# Door_locking_pcb.net
KiCad netlist of a schematic drawn in EAGLE
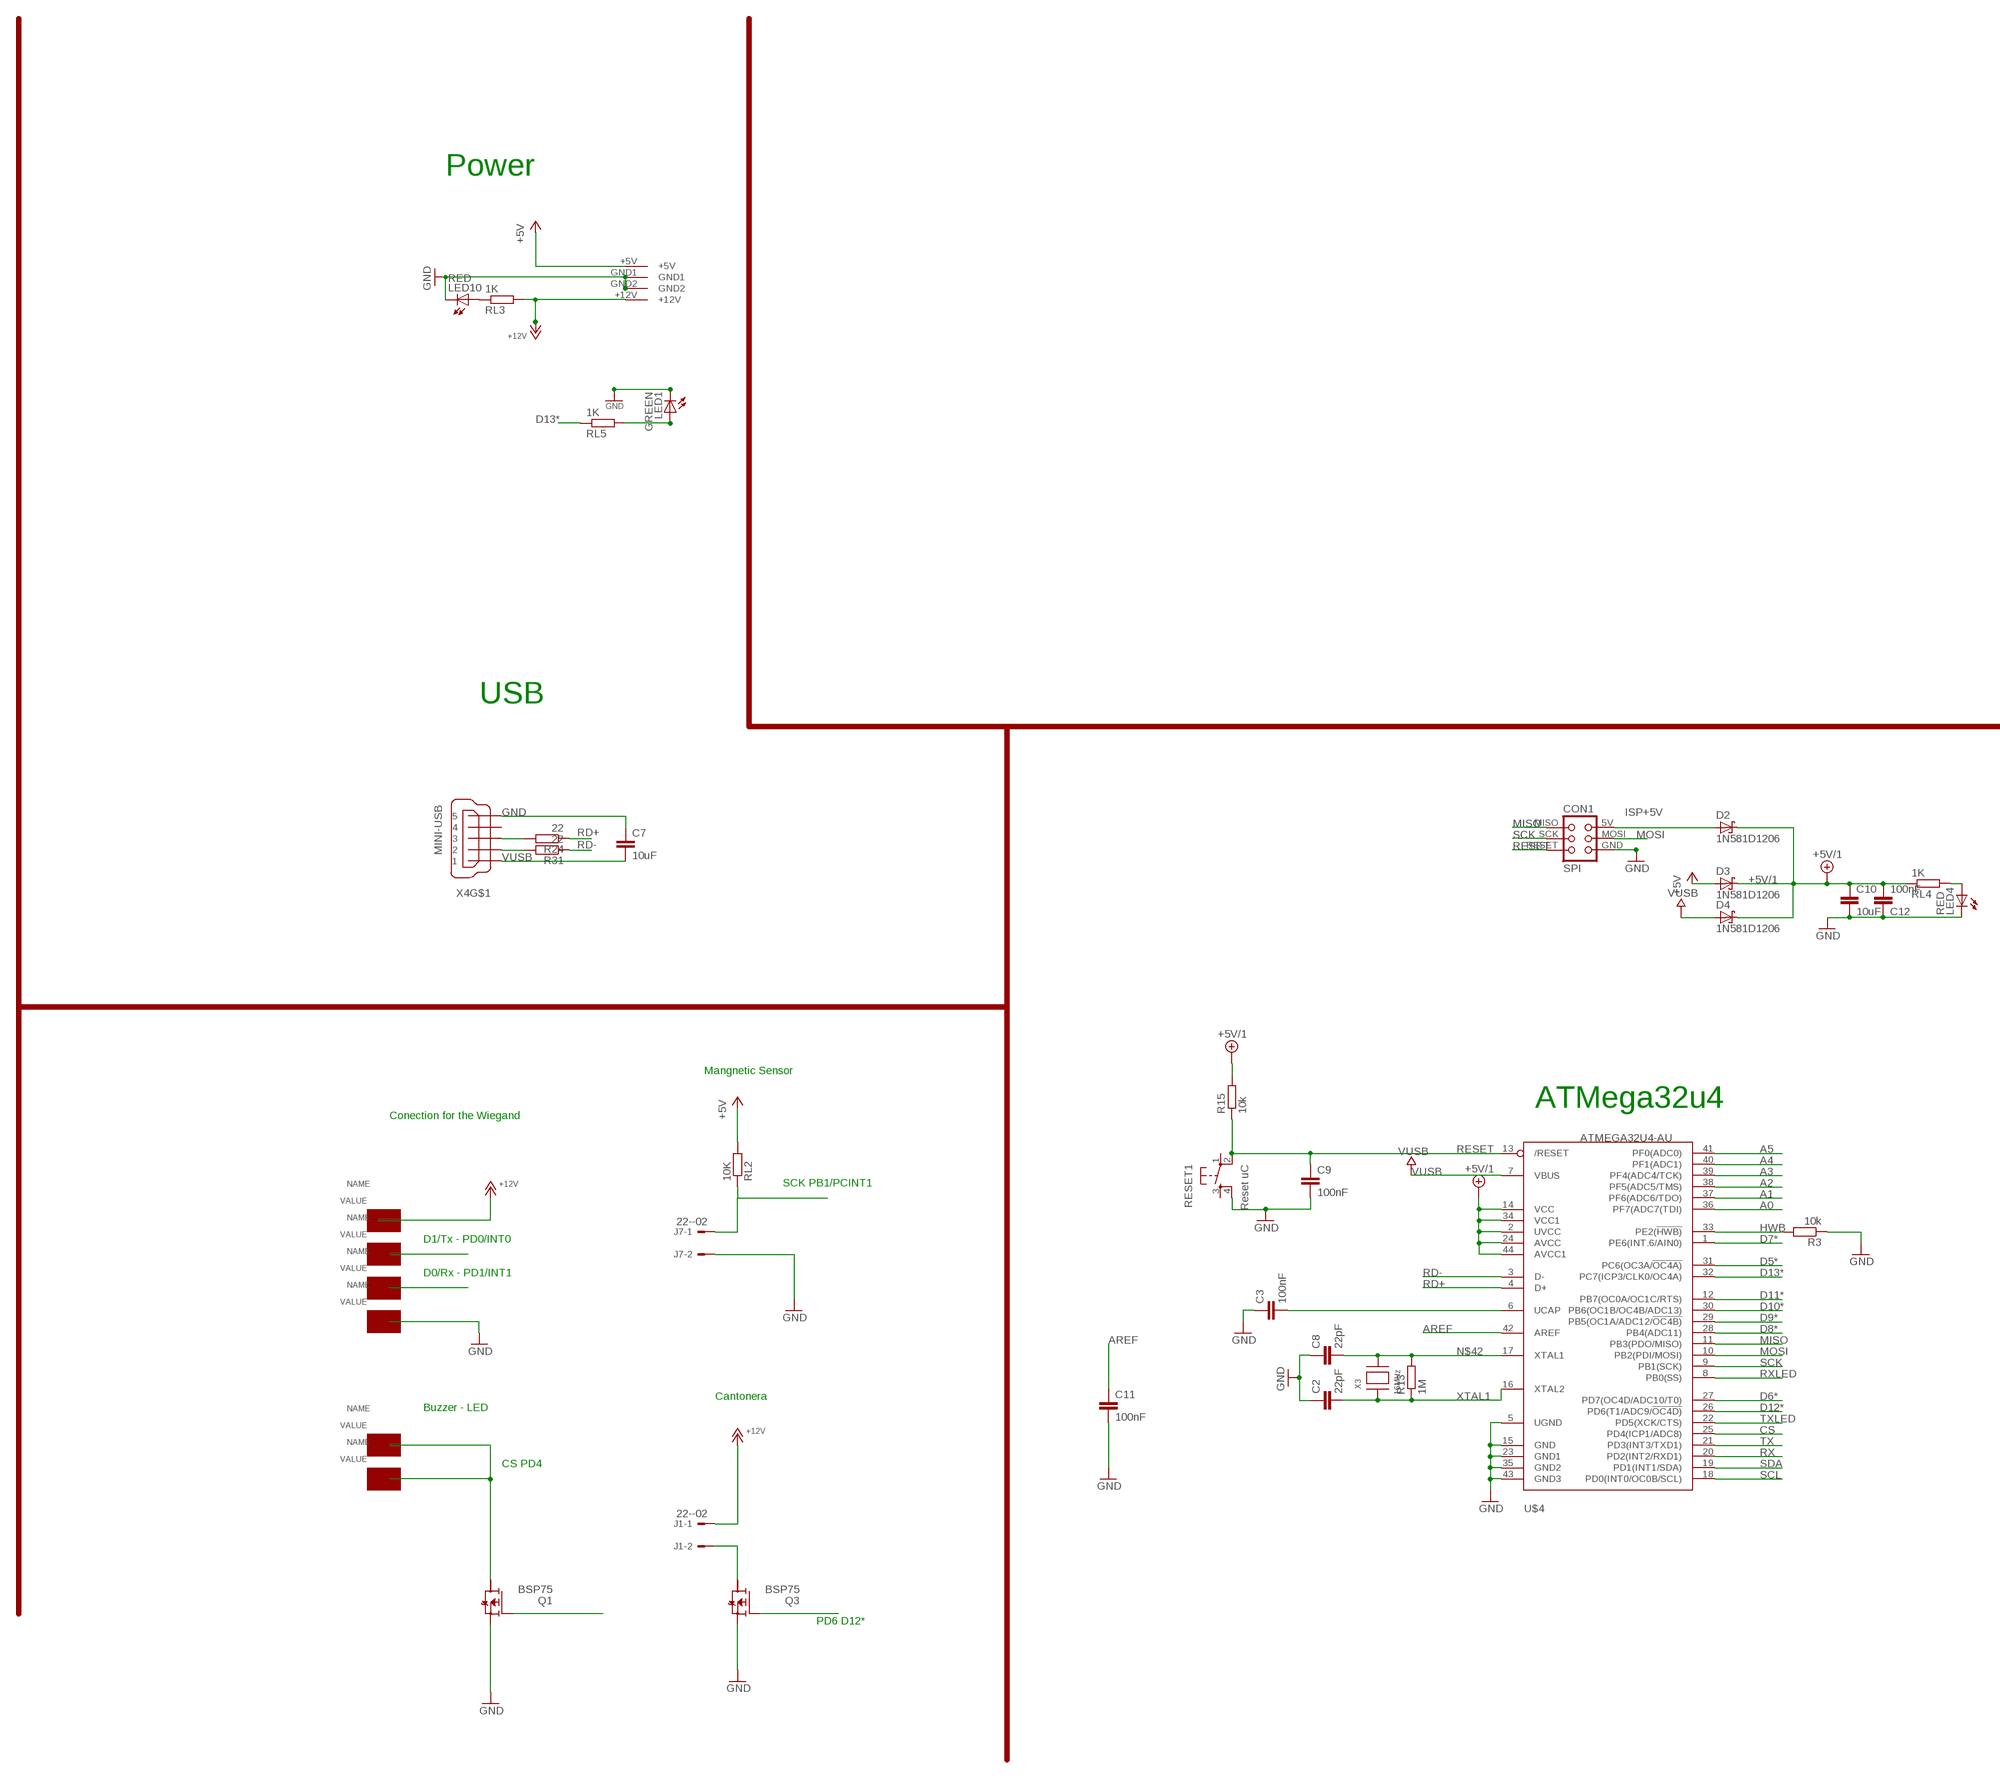
[diagram p0: schematic, sheet 1, part 1 of 2]
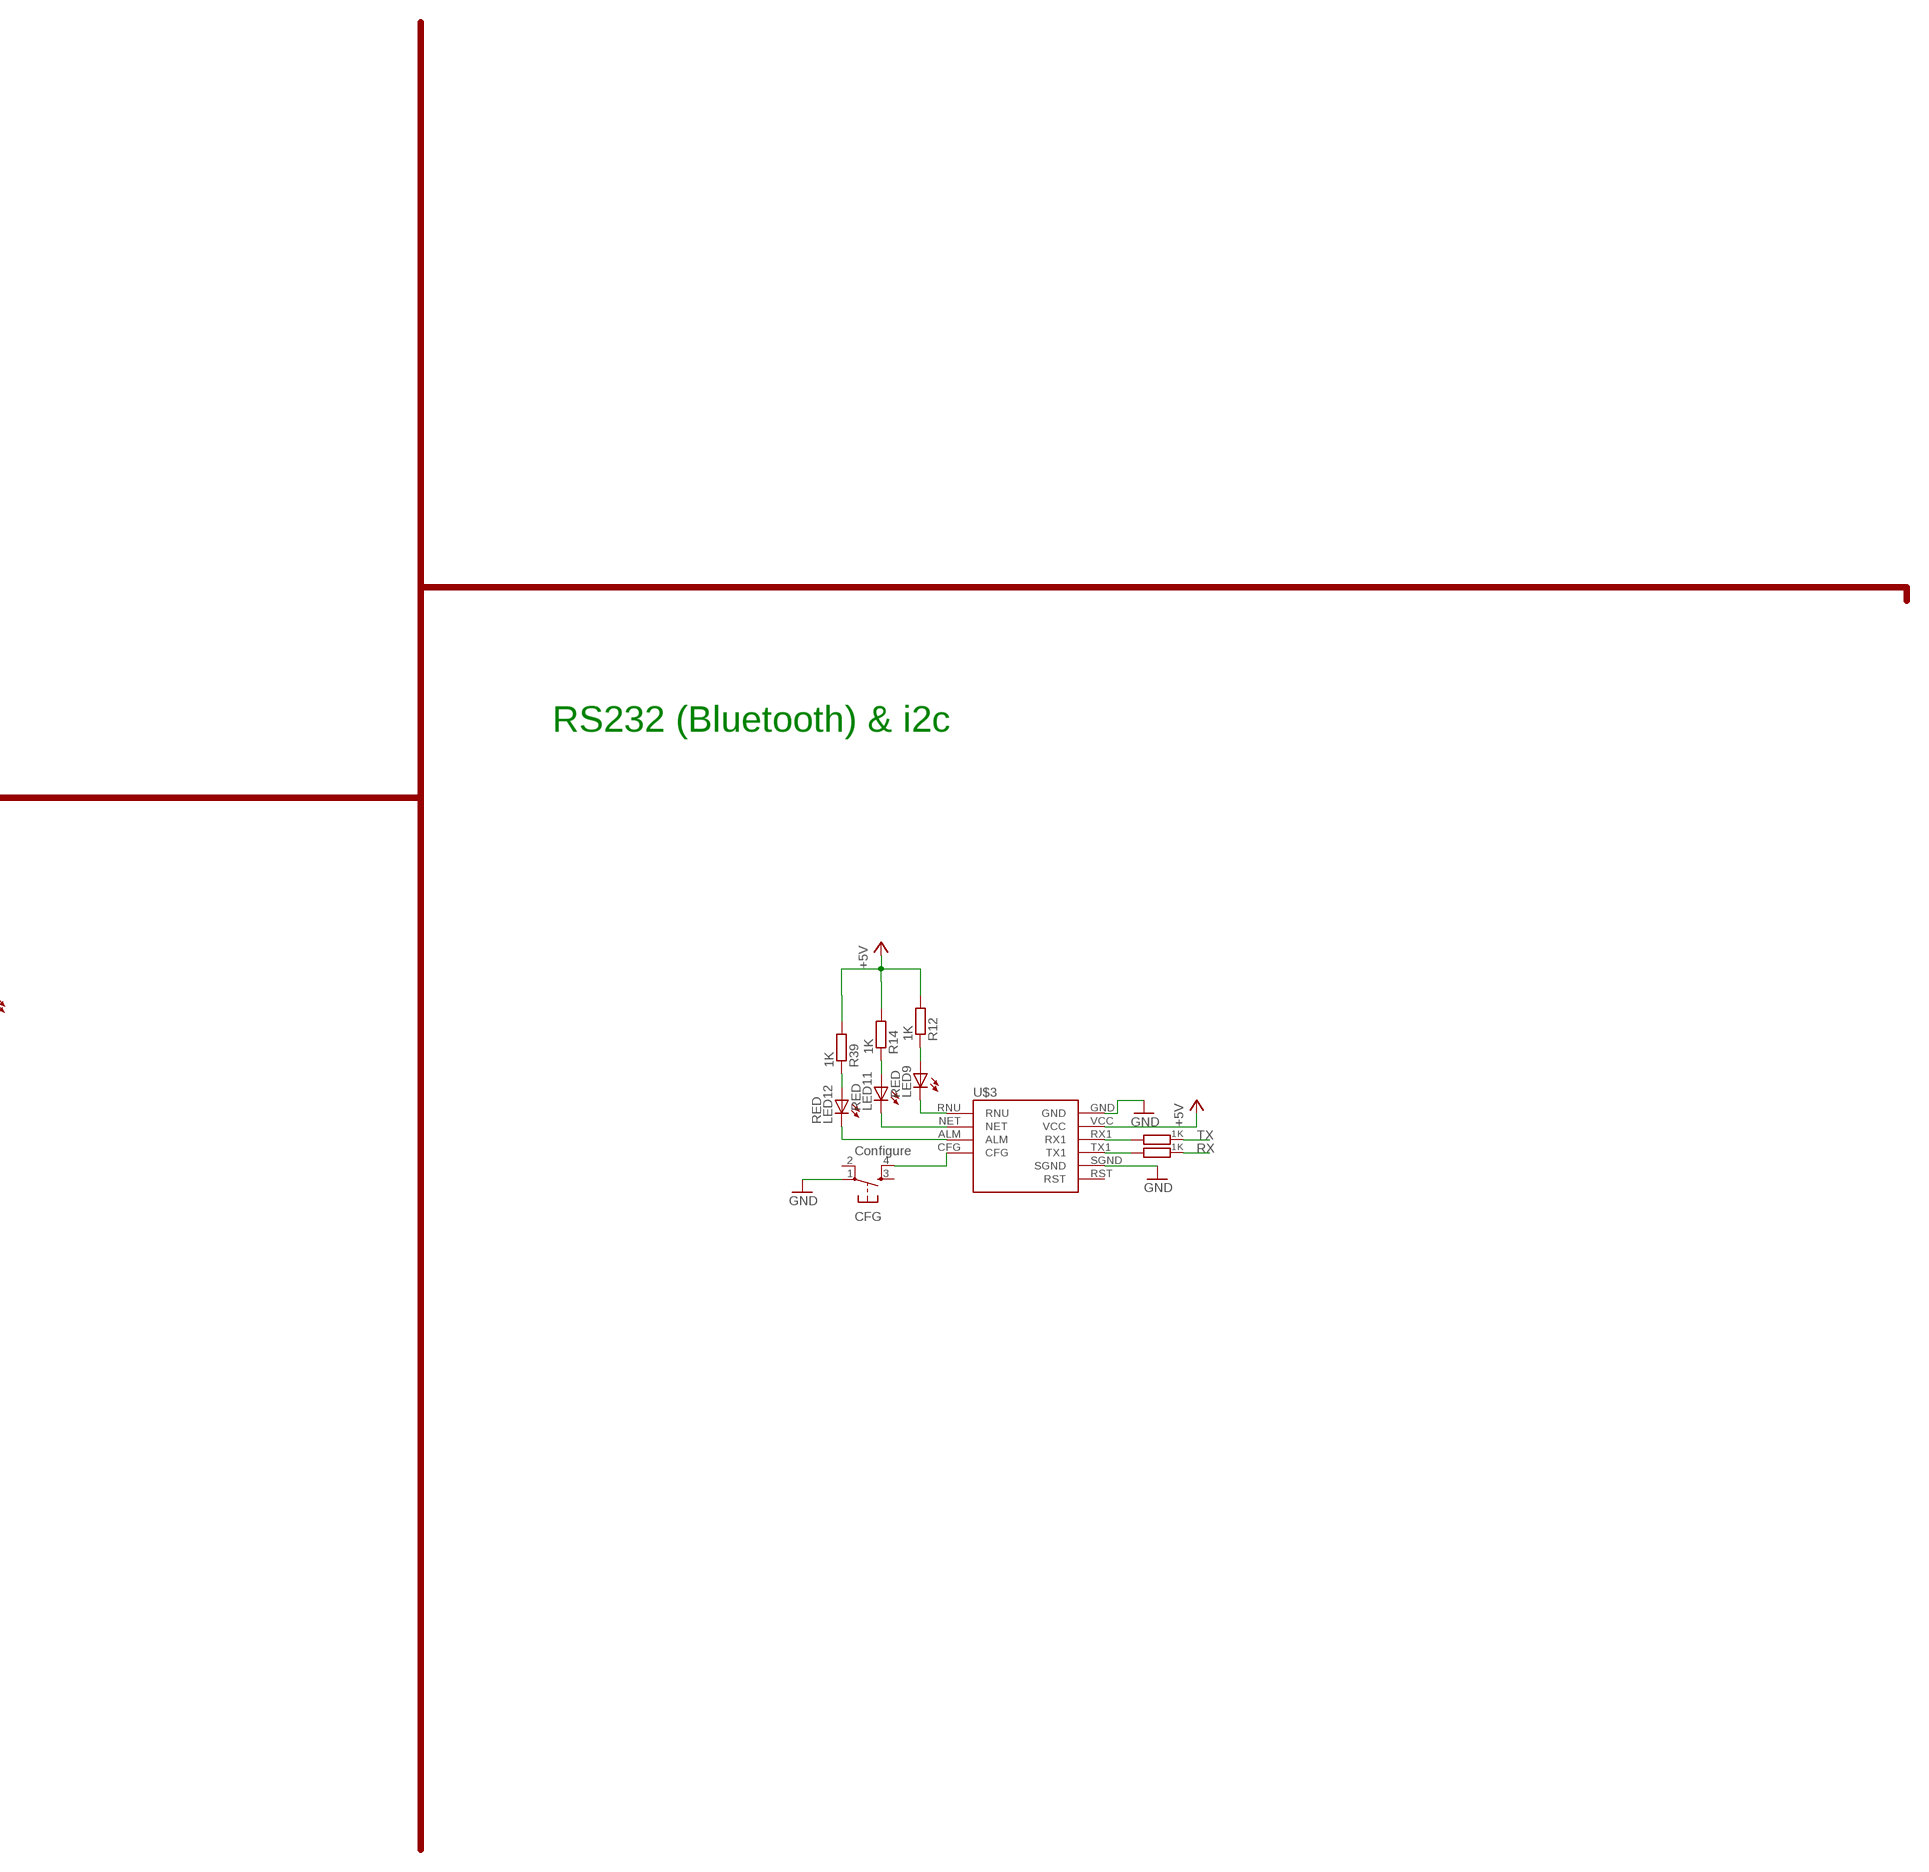
[diagram p1: schematic, sheet 1, part 2 of 2]

(export (version "E")
  (design (tool "Eeschema 10.0.6"))
  (components
    (comp (ref "C2")
      (value "22pF")
      (footprint "eagle-import:C1206")
      (libsource (lib "eagle-import") (part "C-EUC1206"))
    )
    (comp (ref "C3")
      (value "100nF")
      (footprint "eagle-import:C1206")
      (libsource (lib "eagle-import") (part "C-EUC1206"))
    )
    (comp (ref "C7")
      (value "10uF")
      (footprint "eagle-import:C1206")
      (libsource (lib "eagle-import") (part "C-EUC1206"))
    )
    (comp (ref "C8")
      (value "22pF")
      (footprint "eagle-import:C1206")
      (libsource (lib "eagle-import") (part "C-EUC1206"))
    )
    (comp (ref "C9")
      (value "100nF")
      (footprint "eagle-import:C1206")
      (libsource (lib "eagle-import") (part "C-EUC1206"))
    )
    (comp (ref "C10")
      (value "10uF")
      (footprint "eagle-import:C1206")
      (libsource (lib "eagle-import") (part "C-EUC1206"))
    )
    (comp (ref "C11")
      (value "100nF")
      (footprint "eagle-import:C1206")
      (libsource (lib "eagle-import") (part "C-EUC1206"))
    )
    (comp (ref "C12")
      (value "100nF")
      (footprint "eagle-import:C1206")
      (libsource (lib "eagle-import") (part "C-EUC1206"))
    )
    (comp (ref "CFG")
      (value "Configure")
      (footprint "eagle-import:TACTILE_SWITCH_SMD")
      (libsource (lib "eagle-import") (part "TAC_SWITCHSMD"))
    )
    (comp (ref "CON1")
      (value "SPI")
      (footprint "eagle-import:TC2030-MCP-NL")
      (libsource (lib "eagle-import") (part "TINYISPT"))
    )
    (comp (ref "D2")
      (value "1N581D1206")
      (footprint "eagle-import:LED-1206")
      (libsource (lib "eagle-import") (part "1N581D1206"))
    )
    (comp (ref "D3")
      (value "1N581D1206")
      (footprint "eagle-import:LED-1206")
      (libsource (lib "eagle-import") (part "1N581D1206"))
    )
    (comp (ref "D4")
      (value "1N581D1206")
      (footprint "eagle-import:LED-1206")
      (libsource (lib "eagle-import") (part "1N581D1206"))
    )
    (comp (ref "J1")
      (value "22--02")
      (footprint "eagle-import:2-PIN-5.08S")
      (libsource (lib "eagle-import") (part "22-?-02"))
    )
    (comp (ref "J7")
      (value "22--02")
      (footprint "eagle-import:2-PIN-5.08S")
      (libsource (lib "eagle-import") (part "22-?-02"))
    )
    (comp (ref "LED1")
      (value "GREEN")
      (footprint "eagle-import:CHIPLED_1206")
      (libsource (lib "eagle-import") (part "LEDCHIPLED_1206"))
    )
    (comp (ref "LED4")
      (value "RED")
      (footprint "eagle-import:CHIPLED_1206")
      (libsource (lib "eagle-import") (part "LEDCHIPLED_1206"))
    )
    (comp (ref "LED9")
      (value "RED")
      (footprint "eagle-import:CHIPLED_1206")
      (libsource (lib "eagle-import") (part "LEDCHIPLED_1206"))
    )
    (comp (ref "LED10")
      (value "RED")
      (footprint "eagle-import:CHIPLED_1206")
      (libsource (lib "eagle-import") (part "LEDCHIPLED_1206"))
    )
    (comp (ref "LED11")
      (value "RED")
      (footprint "eagle-import:CHIPLED_1206")
      (libsource (lib "eagle-import") (part "LEDCHIPLED_1206"))
    )
    (comp (ref "LED12")
      (value "RED")
      (footprint "eagle-import:CHIPLED_1206")
      (libsource (lib "eagle-import") (part "LEDCHIPLED_1206"))
    )
    (comp (ref "PIN1")
      (value "TERMINALSUPERFICIAL")
      (footprint "eagle-import:ELPUTAS")
      (libsource (lib "eagle-import") (part "TERMINALSUPERFICIAL"))
    )
    (comp (ref "PIN2")
      (value "TERMINALSUPERFICIAL")
      (footprint "eagle-import:ELPUTAS")
      (libsource (lib "eagle-import") (part "TERMINALSUPERFICIAL"))
    )
    (comp (ref "PIN3")
      (value "TERMINALSUPERFICIAL")
      (footprint "eagle-import:ELPUTAS")
      (libsource (lib "eagle-import") (part "TERMINALSUPERFICIAL"))
    )
    (comp (ref "PIN4")
      (value "TERMINALSUPERFICIAL")
      (footprint "eagle-import:ELPUTAS")
      (libsource (lib "eagle-import") (part "TERMINALSUPERFICIAL"))
    )
    (comp (ref "PIN5")
      (value "TERMINALSUPERFICIAL")
      (footprint "eagle-import:ELPUTAS")
      (libsource (lib "eagle-import") (part "TERMINALSUPERFICIAL"))
    )
    (comp (ref "PIN6")
      (value "TERMINALSUPERFICIAL")
      (footprint "eagle-import:ELPUTAS")
      (libsource (lib "eagle-import") (part "TERMINALSUPERFICIAL"))
    )
    (comp (ref "Q1")
      (value "BSP75")
      (footprint "eagle-import:PG-SOT-223")
      (libsource (lib "eagle-import") (part "BSP613P"))
    )
    (comp (ref "Q3")
      (value "BSP75")
      (footprint "eagle-import:PG-SOT-223")
      (libsource (lib "eagle-import") (part "BSP613P"))
    )
    (comp (ref "R3")
      (value "10k")
      (footprint "eagle-import:M0805")
      (libsource (lib "eagle-import") (part "resistor_R-EU_M0805"))
    )
    (comp (ref "R8")
      (value "1K")
      (footprint "eagle-import:R0805")
      (libsource (lib "eagle-import") (part "R-EU_R0805"))
    )
    (comp (ref "R11")
      (value "1K")
      (footprint "eagle-import:R0805")
      (libsource (lib "eagle-import") (part "R-EU_R0805"))
    )
    (comp (ref "R12")
      (value "1K")
      (footprint "eagle-import:R0805")
      (libsource (lib "eagle-import") (part "R-EU_R0805"))
    )
    (comp (ref "R13")
      (value "1M")
      (footprint "eagle-import:R1206")
      (libsource (lib "eagle-import") (part "R-EU_R1206"))
    )
    (comp (ref "R14")
      (value "1K")
      (footprint "eagle-import:R0805")
      (libsource (lib "eagle-import") (part "R-EU_R0805"))
    )
    (comp (ref "R15")
      (value "10k")
      (footprint "eagle-import:M0805")
      (libsource (lib "eagle-import") (part "resistor_R-EU_M0805"))
    )
    (comp (ref "R24")
      (value "22")
      (footprint "eagle-import:M1206")
      (libsource (lib "eagle-import") (part "resistor_R-EU_M1206"))
    )
    (comp (ref "R31")
      (value "22")
      (footprint "eagle-import:M1206")
      (libsource (lib "eagle-import") (part "resistor_R-EU_M1206"))
    )
    (comp (ref "R39")
      (value "1K")
      (footprint "eagle-import:R0805")
      (libsource (lib "eagle-import") (part "R-EU_R0805"))
    )
    (comp (ref "RESET1")
      (value "Reset uC")
      (footprint "eagle-import:TACTILE_SWITCH_SMD")
      (libsource (lib "eagle-import") (part "TAC_SWITCHSMD"))
    )
    (comp (ref "RL2")
      (value "10K")
      (footprint "eagle-import:R0805")
      (libsource (lib "eagle-import") (part "R-EU_R0805"))
    )
    (comp (ref "RL3")
      (value "1K")
      (footprint "eagle-import:R0805")
      (libsource (lib "eagle-import") (part "R-EU_R0805"))
    )
    (comp (ref "RL4")
      (value "1K")
      (footprint "eagle-import:R0805")
      (libsource (lib "eagle-import") (part "resistor_R-EU_R0805"))
    )
    (comp (ref "RL5")
      (value "1K")
      (footprint "eagle-import:R0805")
      (libsource (lib "eagle-import") (part "R-EU_R0805"))
    )
    (comp (ref "U$3")
      (value "SZ05-ZIGBEE")
      (footprint "eagle-import:SZ05-ZIGBEE")
      (libsource (lib "eagle-import") (part "SZ05-ZIGBEE"))
    )
    (comp (ref "U$4")
      (value "ATMEGA32U4-AU")
      (footprint "eagle-import:TQFP44")
      (libsource (lib "eagle-import") (part "ATMEGA32U4-AU"))
    )
    (comp (ref "U$6")
      (value "KPJX-4S-S")
      (footprint "eagle-import:KPJX-4S-S")
      (libsource (lib "eagle-import") (part "KPJX-4S-S"))
    )
    (comp (ref "X3")
      (value "16MHz")
      (footprint "eagle-import:NX6035")
      (libsource (lib "eagle-import") (part "XTALNX6035"))
    )
    (comp (ref "X4")
      (value "MINI-USB")
      (footprint "eagle-import:32005-201")
      (libsource (lib "eagle-import") (part "MINI-USB-SCHIELD-32005-201"))
    )
  )
  (nets
    (net (code "1") (name "+5V") (class "Default")
      (node (ref "D3") (pin "A") (pinfunction "A_A") (pintype "passive"))
      (node (ref "R12") (pin "2") (pinfunction "2_2") (pintype "passive"))
      (node (ref "R14") (pin "2") (pinfunction "2_2") (pintype "passive"))
      (node (ref "R39") (pin "2") (pinfunction "2_2") (pintype "passive"))
      (node (ref "RL2") (pin "2") (pinfunction "2_2") (pintype "passive"))
      (node (ref "U$3") (pin "VCC") (pinfunction "VCC_VCC") (pintype "bidirectional"))
      (node (ref "U$6") (pin "+5V") (pinfunction "+5V_+5V") (pintype "power_in"))
    )
    (net (code "2") (name "+5V{slash}1") (class "Default")
      (node (ref "C10") (pin "1") (pinfunction "1_1") (pintype "passive"))
      (node (ref "C12") (pin "2") (pinfunction "2_2") (pintype "passive"))
      (node (ref "D2") (pin "C") (pinfunction "C_C") (pintype "passive"))
      (node (ref "D3") (pin "C") (pinfunction "C_C") (pintype "passive"))
      (node (ref "D4") (pin "C") (pinfunction "C_C") (pintype "passive"))
      (node (ref "R15") (pin "2") (pinfunction "2_2") (pintype "passive"))
      (node (ref "RL4") (pin "1") (pinfunction "1_1") (pintype "passive"))
      (node (ref "U$4") (pin "14") (pinfunction "VCC_14") (pintype "bidirectional"))
      (node (ref "U$4") (pin "2") (pinfunction "UVCC_2") (pintype "bidirectional"))
      (node (ref "U$4") (pin "24") (pinfunction "AVCC_24") (pintype "bidirectional"))
      (node (ref "U$4") (pin "34") (pinfunction "VCC1_34") (pintype "bidirectional"))
      (node (ref "U$4") (pin "44") (pinfunction "AVCC1_44") (pintype "bidirectional"))
    )
    (net (code "3") (name "+12V") (class "Default")
      (node (ref "J1") (pin "1") (pinfunction "S_1") (pintype "passive"))
      (node (ref "PIN6") (pin "P$4") (pinfunction "2_P$4") (pintype "bidirectional"))
      (node (ref "RL3") (pin "2") (pinfunction "2_2") (pintype "passive"))
      (node (ref "U$6") (pin "+12V") (pinfunction "+12V_+12V") (pintype "power_in"))
    )
    (net (code "4") (name "/A0") (class "Default")
      (node (ref "U$4") (pin "36") (pinfunction "PF7(ADC7(TDI)_36") (pintype "bidirectional"))
    )
    (net (code "5") (name "/A1") (class "Default")
      (node (ref "U$4") (pin "37") (pinfunction "PF6(ADC6/TDO)_37") (pintype "bidirectional"))
    )
    (net (code "6") (name "/A2") (class "Default")
      (node (ref "U$4") (pin "38") (pinfunction "PF5(ADC5/TMS)_38") (pintype "bidirectional"))
    )
    (net (code "7") (name "/A3") (class "Default")
      (node (ref "U$4") (pin "39") (pinfunction "PF4(ADC4/TCK)_39") (pintype "bidirectional"))
    )
    (net (code "8") (name "/A4") (class "Default")
      (node (ref "U$4") (pin "40") (pinfunction "PF1(ADC1)_40") (pintype "bidirectional"))
    )
    (net (code "9") (name "/A5") (class "Default")
      (node (ref "U$4") (pin "41") (pinfunction "PF0(ADC0)_41") (pintype "bidirectional"))
    )
    (net (code "10") (name "/AREF") (class "Default")
      (node (ref "C11") (pin "1") (pinfunction "1_1") (pintype "passive"))
      (node (ref "U$4") (pin "42") (pinfunction "AREF_42") (pintype "bidirectional"))
    )
    (net (code "11") (name "/CS") (class "Default")
      (node (ref "Q1") (pin "1") (pinfunction "G_1") (pintype "passive"))
      (node (ref "U$4") (pin "25") (pinfunction "PD4(ICP1/ADC8)_25") (pintype "bidirectional"))
    )
    (net (code "12") (name "/D5*") (class "Default")
      (node (ref "U$4") (pin "31") (pinfunction "PC6(OC3A/~{OC4A})_31") (pintype "bidirectional"))
    )
    (net (code "13") (name "/D6*") (class "Default")
      (node (ref "U$4") (pin "27") (pinfunction "PD7(OC4D/ADC10/T0)_27") (pintype "bidirectional"))
    )
    (net (code "14") (name "/D7*") (class "Default")
      (node (ref "U$4") (pin "1") (pinfunction "PE6(INT.6/AIN0)_1") (pintype "bidirectional"))
    )
    (net (code "15") (name "/D8*") (class "Default")
      (node (ref "U$4") (pin "28") (pinfunction "PB4(ADC11)_28") (pintype "bidirectional"))
    )
    (net (code "16") (name "/D9*") (class "Default")
      (node (ref "U$4") (pin "29") (pinfunction "PB5(OC1A/ADC12/~{OC4B})_29") (pintype "bidirectional"))
    )
    (net (code "17") (name "/D10*") (class "Default")
      (node (ref "U$4") (pin "30") (pinfunction "PB6(OC1B/OC4B/ADC13)_30") (pintype "bidirectional"))
    )
    (net (code "18") (name "/D11*") (class "Default")
      (node (ref "U$4") (pin "12") (pinfunction "PB7(OC0A/OC1C/RTS)_12") (pintype "bidirectional"))
    )
    (net (code "19") (name "/D12*") (class "Default")
      (node (ref "Q3") (pin "1") (pinfunction "G_1") (pintype "passive"))
      (node (ref "U$4") (pin "26") (pinfunction "PD6(T1/ADC9/~{OC4D})_26") (pintype "bidirectional"))
    )
    (net (code "20") (name "/D13*") (class "Default")
      (node (ref "RL5") (pin "1") (pinfunction "1_1") (pintype "passive"))
      (node (ref "U$4") (pin "32") (pinfunction "PC7(ICP3/CLK0/OC4A)_32") (pintype "bidirectional"))
    )
    (net (code "21") (name "/HWB") (class "Default")
      (node (ref "R3") (pin "2") (pinfunction "2_2") (pintype "passive"))
      (node (ref "U$4") (pin "33") (pinfunction "PE2(~{HWB})_33") (pintype "bidirectional"))
    )
    (net (code "22") (name "/ISP+5V") (class "Default")
      (node (ref "CON1") (pin "5V") (pinfunction "VCC_5V") (pintype "passive"))
      (node (ref "D2") (pin "A") (pinfunction "A_A") (pintype "passive"))
    )
    (net (code "23") (name "/MISO") (class "Default")
      (node (ref "CON1") (pin "MISO") (pinfunction "MISO_MISO") (pintype "passive"))
      (node (ref "U$4") (pin "11") (pinfunction "PB3(PDO/MISO)_11") (pintype "bidirectional"))
    )
    (net (code "24") (name "/MOSI") (class "Default")
      (node (ref "CON1") (pin "MOSI") (pinfunction "MOSI_MOSI") (pintype "passive"))
      (node (ref "U$4") (pin "10") (pinfunction "PB2(PDI/MOSI)_10") (pintype "bidirectional"))
    )
    (net (code "25") (name "/N$42") (class "Default")
      (node (ref "C8") (pin "2") (pinfunction "2_2") (pintype "passive"))
      (node (ref "R13") (pin "2") (pinfunction "2_2") (pintype "passive"))
      (node (ref "U$4") (pin "17") (pinfunction "XTAL1_17") (pintype "bidirectional"))
      (node (ref "X3") (pin "P$2") (pinfunction "P$2_P$2") (pintype "bidirectional"))
    )
    (net (code "26") (name "/RD+") (class "Default")
      (node (ref "R24") (pin "1") (pinfunction "1_1") (pintype "passive"))
      (node (ref "U$4") (pin "4") (pinfunction "D+_4") (pintype "bidirectional"))
    )
    (net (code "27") (name "/RD-") (class "Default")
      (node (ref "R31") (pin "1") (pinfunction "1_1") (pintype "passive"))
      (node (ref "U$4") (pin "3") (pinfunction "D-_3") (pintype "bidirectional"))
    )
    (net (code "28") (name "/RESET") (class "Default")
      (node (ref "C9") (pin "1") (pinfunction "1_1") (pintype "passive"))
      (node (ref "CON1") (pin "RESET") (pinfunction "RESET_RESET") (pintype "passive"))
      (node (ref "R15") (pin "1") (pinfunction "1_1") (pintype "passive"))
      (node (ref "RESET1") (pin "2") (pinfunction "2_2") (pintype "passive"))
      (node (ref "U$4") (pin "13") (pinfunction "/RESET_13") (pintype "bidirectional"))
    )
    (net (code "29") (name "/RX") (class "Default")
      (node (ref "R8") (pin "1") (pinfunction "1_1") (pintype "passive"))
      (node (ref "U$4") (pin "20") (pinfunction "PD2(INT2/RXD1)_20") (pintype "bidirectional"))
    )
    (net (code "30") (name "/RXLED") (class "Default")
      (node (ref "U$4") (pin "8") (pinfunction "PB0(SS)_8") (pintype "bidirectional"))
    )
    (net (code "31") (name "/SCK") (class "Default")
      (node (ref "CON1") (pin "SCK") (pinfunction "SCK_SCK") (pintype "passive"))
      (node (ref "J7") (pin "1") (pinfunction "S_1") (pintype "passive"))
      (node (ref "RL2") (pin "1") (pinfunction "1_1") (pintype "passive"))
      (node (ref "U$4") (pin "9") (pinfunction "PB1(SCK)_9") (pintype "bidirectional"))
    )
    (net (code "32") (name "/SCL") (class "Default")
      (node (ref "PIN1") (pin "P$3") (pinfunction "1_P$3") (pintype "bidirectional"))
      (node (ref "U$4") (pin "18") (pinfunction "PD0(INT0/OC0B/SCL)_18") (pintype "bidirectional"))
    )
    (net (code "33") (name "/SDA") (class "Default")
      (node (ref "PIN2") (pin "P$3") (pinfunction "1_P$3") (pintype "bidirectional"))
      (node (ref "U$4") (pin "19") (pinfunction "PD1(INT1/SDA)_19") (pintype "bidirectional"))
    )
    (net (code "34") (name "/TX") (class "Default")
      (node (ref "R11") (pin "1") (pinfunction "1_1") (pintype "passive"))
      (node (ref "U$4") (pin "21") (pinfunction "PD3(INT3/TXD1)_21") (pintype "bidirectional"))
    )
    (net (code "35") (name "/TXLED") (class "Default")
      (node (ref "U$4") (pin "22") (pinfunction "PD5(XCK/CTS)_22") (pintype "bidirectional"))
    )
    (net (code "36") (name "/XTAL1") (class "Default")
      (node (ref "C2") (pin "2") (pinfunction "2_2") (pintype "passive"))
      (node (ref "R13") (pin "1") (pinfunction "1_1") (pintype "passive"))
      (node (ref "U$4") (pin "16") (pinfunction "XTAL2_16") (pintype "bidirectional"))
      (node (ref "X3") (pin "P$1") (pinfunction "P$1_P$1") (pintype "bidirectional"))
    )
    (net (code "37") (name "GND") (class "Default")
      (node (ref "C10") (pin "2") (pinfunction "2_2") (pintype "passive"))
      (node (ref "C11") (pin "2") (pinfunction "2_2") (pintype "passive"))
      (node (ref "C12") (pin "1") (pinfunction "1_1") (pintype "passive"))
      (node (ref "C2") (pin "1") (pinfunction "1_1") (pintype "passive"))
      (node (ref "C3") (pin "1") (pinfunction "1_1") (pintype "passive"))
      (node (ref "C7") (pin "1") (pinfunction "1_1") (pintype "passive"))
      (node (ref "C8") (pin "1") (pinfunction "1_1") (pintype "passive"))
      (node (ref "C9") (pin "2") (pinfunction "2_2") (pintype "passive"))
      (node (ref "CFG") (pin "1") (pinfunction "1_1") (pintype "passive"))
      (node (ref "CON1") (pin "GND") (pinfunction "GND_GND") (pintype "passive"))
      (node (ref "J7") (pin "2") (pinfunction "S_2") (pintype "passive"))
      (node (ref "LED1") (pin "C") (pinfunction "C_C") (pintype "passive"))
      (node (ref "LED10") (pin "C") (pinfunction "C_C") (pintype "passive"))
      (node (ref "LED4") (pin "C") (pinfunction "C_C") (pintype "passive"))
      (node (ref "PIN5") (pin "P$3") (pinfunction "1_P$3") (pintype "bidirectional"))
      (node (ref "Q1") (pin "3") (pinfunction "S_3") (pintype "passive"))
      (node (ref "Q3") (pin "3") (pinfunction "S_3") (pintype "passive"))
      (node (ref "R3") (pin "1") (pinfunction "1_1") (pintype "passive"))
      (node (ref "RESET1") (pin "4") (pinfunction "4_4") (pintype "passive"))
      (node (ref "U$3") (pin "GND") (pinfunction "GND_GND") (pintype "bidirectional"))
      (node (ref "U$3") (pin "SGND") (pinfunction "SGND_SGND") (pintype "bidirectional"))
      (node (ref "U$4") (pin "15") (pinfunction "GND_15") (pintype "bidirectional"))
      (node (ref "U$4") (pin "23") (pinfunction "GND1_23") (pintype "bidirectional"))
      (node (ref "U$4") (pin "35") (pinfunction "GND2_35") (pintype "bidirectional"))
      (node (ref "U$4") (pin "43") (pinfunction "GND3_43") (pintype "bidirectional"))
      (node (ref "U$4") (pin "5") (pinfunction "UGND_5") (pintype "bidirectional"))
      (node (ref "U$6") (pin "GND1") (pinfunction "GND1_GND1") (pintype "input"))
      (node (ref "U$6") (pin "GND2") (pinfunction "GND2_GND2") (pintype "input"))
      (node (ref "X4") (pin "5") (pinfunction "5_5") (pintype "passive"))
    )
    (net (code "38") (name "Net-(CFG-Pad4)") (class "Default")
      (node (ref "CFG") (pin "4") (pinfunction "4_4") (pintype "passive"))
      (node (ref "U$3") (pin "CFG") (pinfunction "CFG_CFG") (pintype "bidirectional"))
    )
    (net (code "39") (name "Net-(J1B-S)") (class "Default")
      (node (ref "J1") (pin "2") (pinfunction "S_2") (pintype "passive"))
      (node (ref "Q3") (pin "2") (pinfunction "D_2") (pintype "passive"))
    )
    (net (code "40") (name "Net-(LED1-PadA)") (class "Default")
      (node (ref "LED1") (pin "A") (pinfunction "A_A") (pintype "passive"))
      (node (ref "RL5") (pin "2") (pinfunction "2_2") (pintype "passive"))
    )
    (net (code "41") (name "Net-(LED4-PadA)") (class "Default")
      (node (ref "LED4") (pin "A") (pinfunction "A_A") (pintype "passive"))
      (node (ref "RL4") (pin "2") (pinfunction "2_2") (pintype "passive"))
    )
    (net (code "42") (name "Net-(LED9-PadA)") (class "Default")
      (node (ref "LED9") (pin "A") (pinfunction "A_A") (pintype "passive"))
      (node (ref "R12") (pin "1") (pinfunction "1_1") (pintype "passive"))
    )
    (net (code "43") (name "Net-(LED9-PadC)") (class "Default")
      (node (ref "LED9") (pin "C") (pinfunction "C_C") (pintype "passive"))
      (node (ref "U$3") (pin "RNU") (pinfunction "RNU_RNU") (pintype "bidirectional"))
    )
    (net (code "44") (name "Net-(LED10-PadA)") (class "Default")
      (node (ref "LED10") (pin "A") (pinfunction "A_A") (pintype "passive"))
      (node (ref "RL3") (pin "1") (pinfunction "1_1") (pintype "passive"))
    )
    (net (code "45") (name "Net-(LED11-PadA)") (class "Default")
      (node (ref "LED11") (pin "A") (pinfunction "A_A") (pintype "passive"))
      (node (ref "R14") (pin "1") (pinfunction "1_1") (pintype "passive"))
    )
    (net (code "46") (name "Net-(LED11-PadC)") (class "Default")
      (node (ref "LED11") (pin "C") (pinfunction "C_C") (pintype "passive"))
      (node (ref "U$3") (pin "NET") (pinfunction "NET_NET") (pintype "bidirectional"))
    )
    (net (code "47") (name "Net-(LED12-PadA)") (class "Default")
      (node (ref "LED12") (pin "A") (pinfunction "A_A") (pintype "passive"))
      (node (ref "R39") (pin "1") (pinfunction "1_1") (pintype "passive"))
    )
    (net (code "48") (name "Net-(LED12-PadC)") (class "Default")
      (node (ref "LED12") (pin "C") (pinfunction "C_C") (pintype "passive"))
      (node (ref "U$3") (pin "ALM") (pinfunction "ALM_ALM") (pintype "bidirectional"))
    )
    (net (code "49") (name "Net-(PIN3-1)") (class "Default")
      (node (ref "PIN3") (pin "P$3") (pinfunction "1_P$3") (pintype "bidirectional"))
      (node (ref "PIN4") (pin "P$3") (pinfunction "1_P$3") (pintype "bidirectional"))
      (node (ref "Q1") (pin "2") (pinfunction "D_2") (pintype "passive"))
    )
    (net (code "50") (name "Net-(R8-Pad2)") (class "Default")
      (node (ref "R8") (pin "2") (pinfunction "2_2") (pintype "passive"))
      (node (ref "U$3") (pin "TX1") (pinfunction "TX1_TX1") (pintype "bidirectional"))
    )
    (net (code "51") (name "Net-(R11-Pad2)") (class "Default")
      (node (ref "R11") (pin "2") (pinfunction "2_2") (pintype "passive"))
      (node (ref "U$3") (pin "RX1") (pinfunction "RX1_RX1") (pintype "bidirectional"))
    )
    (net (code "52") (name "Net-(R24-Pad2)") (class "Default")
      (node (ref "R24") (pin "2") (pinfunction "2_2") (pintype "passive"))
      (node (ref "X4") (pin "3") (pinfunction "3_3") (pintype "passive"))
    )
    (net (code "53") (name "Net-(R31-Pad2)") (class "Default")
      (node (ref "R31") (pin "2") (pinfunction "2_2") (pintype "passive"))
      (node (ref "X4") (pin "2") (pinfunction "2_2") (pintype "passive"))
    )
    (net (code "54") (name "Net-(U$4-UCAP)") (class "Default")
      (node (ref "C3") (pin "2") (pinfunction "2_2") (pintype "passive"))
      (node (ref "U$4") (pin "6") (pinfunction "UCAP_6") (pintype "bidirectional"))
    )
    (net (code "55") (name "VUSB") (class "Default")
      (node (ref "C7") (pin "2") (pinfunction "2_2") (pintype "passive"))
      (node (ref "D4") (pin "A") (pinfunction "A_A") (pintype "passive"))
      (node (ref "U$4") (pin "7") (pinfunction "VBUS_7") (pintype "bidirectional"))
      (node (ref "X4") (pin "1") (pinfunction "1_1") (pintype "passive"))
    )
    (net (code "56") (name "unconnected-(CFG-Pad2)") (class "Default")
      (node (ref "CFG") (pin "2") (pinfunction "2_2") (pintype "passive"))
    )
    (net (code "57") (name "unconnected-(CFG-Pad3)") (class "Default")
      (node (ref "CFG") (pin "3") (pinfunction "3_3") (pintype "passive"))
    )
    (net (code "58") (name "unconnected-(PIN1-2-PadP$4)") (class "Default")
      (node (ref "PIN1") (pin "P$4") (pinfunction "2_P$4") (pintype "bidirectional"))
    )
    (net (code "59") (name "unconnected-(PIN2-2-PadP$4)") (class "Default")
      (node (ref "PIN2") (pin "P$4") (pinfunction "2_P$4") (pintype "bidirectional"))
    )
    (net (code "60") (name "unconnected-(PIN3-2-PadP$4)") (class "Default")
      (node (ref "PIN3") (pin "P$4") (pinfunction "2_P$4") (pintype "bidirectional"))
    )
    (net (code "61") (name "unconnected-(PIN4-2-PadP$4)") (class "Default")
      (node (ref "PIN4") (pin "P$4") (pinfunction "2_P$4") (pintype "bidirectional"))
    )
    (net (code "62") (name "unconnected-(PIN5-2-PadP$4)") (class "Default")
      (node (ref "PIN5") (pin "P$4") (pinfunction "2_P$4") (pintype "bidirectional"))
    )
    (net (code "63") (name "unconnected-(PIN6-1-PadP$3)") (class "Default")
      (node (ref "PIN6") (pin "P$3") (pinfunction "1_P$3") (pintype "bidirectional"))
    )
    (net (code "64") (name "unconnected-(Q1-D-Pad4)") (class "Default")
      (node (ref "Q1") (pin "4") (pinfunction "D_4") (pintype "passive"))
    )
    (net (code "65") (name "unconnected-(Q3-D-Pad4)") (class "Default")
      (node (ref "Q3") (pin "4") (pinfunction "D_4") (pintype "passive"))
    )
    (net (code "66") (name "unconnected-(RESET1-Pad1)") (class "Default")
      (node (ref "RESET1") (pin "1") (pinfunction "1_1") (pintype "passive"))
    )
    (net (code "67") (name "unconnected-(RESET1-Pad3)") (class "Default")
      (node (ref "RESET1") (pin "3") (pinfunction "3_3") (pintype "passive"))
    )
    (net (code "68") (name "unconnected-(U$3-PadRST)") (class "Default")
      (node (ref "U$3") (pin "RST") (pinfunction "RST_RST") (pintype "bidirectional"))
    )
    (net (code "69") (name "unconnected-(X4-Pad4)") (class "Default")
      (node (ref "X4") (pin "4") (pinfunction "4_4") (pintype "passive"))
    )
  )
)
